# GPIO.net
KiCad netlist of a schematic drawn in Altium Designer
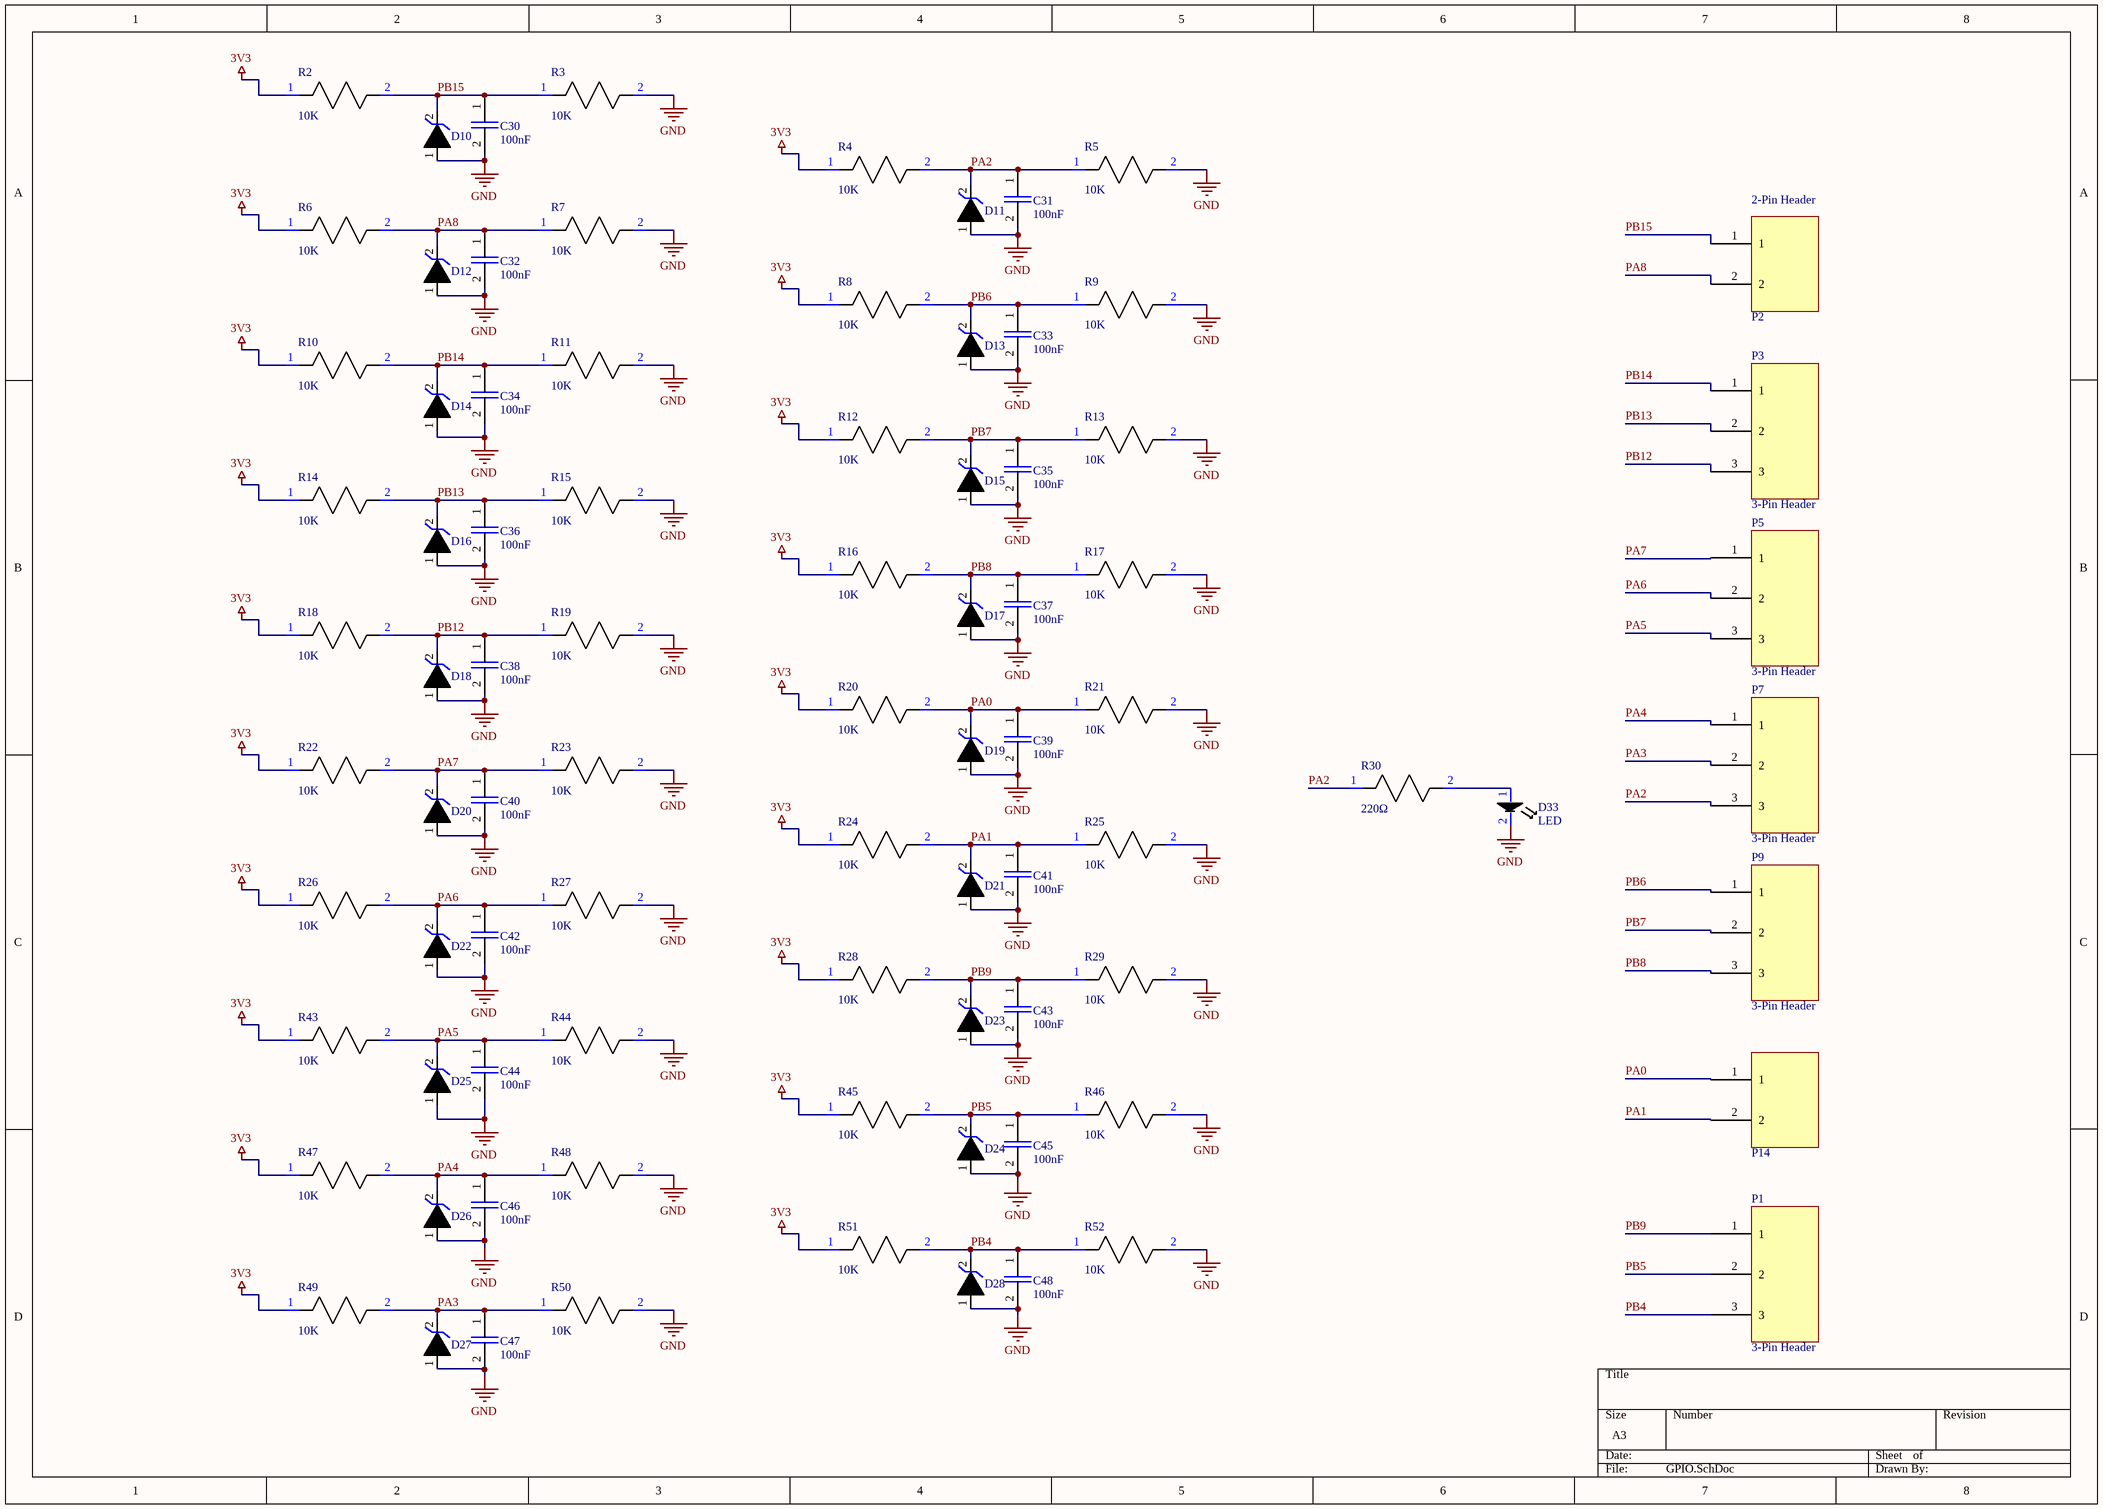
[diagram p0: GPIO.SchDoc]

(export (version "E")
  (design (tool "Eeschema 10.0.6"))
  (components
    (comp (ref "C30")
      (value "100nF")
      (footprint "0603 Cap")
      (description "SMD 0603 (ceramic) capacitor")
      (fields
        (field (name "MANUFACTURER") "Murata")
        (field (name "MANUFACTURER PART NUMBER") "GRM21BR71C225KA12L")
      )
      (libsource (lib "Lib") (part "0603 Cap"))
    )
    (comp (ref "C31")
      (value "100nF")
      (footprint "0603 Cap")
      (description "SMD 0603 (ceramic) capacitor")
      (fields
        (field (name "MANUFACTURER") "Murata")
        (field (name "MANUFACTURER PART NUMBER") "GRM21BR71C225KA12L")
      )
      (libsource (lib "Lib") (part "0603 Cap"))
    )
    (comp (ref "C32")
      (value "100nF")
      (footprint "0603 Cap")
      (description "SMD 0603 (ceramic) capacitor")
      (fields
        (field (name "MANUFACTURER") "Murata")
        (field (name "MANUFACTURER PART NUMBER") "GRM21BR71C225KA12L")
      )
      (libsource (lib "Lib") (part "0603 Cap"))
    )
    (comp (ref "C33")
      (value "100nF")
      (footprint "0603 Cap")
      (description "SMD 0603 (ceramic) capacitor")
      (fields
        (field (name "MANUFACTURER") "Murata")
        (field (name "MANUFACTURER PART NUMBER") "GRM21BR71C225KA12L")
      )
      (libsource (lib "Lib") (part "0603 Cap"))
    )
    (comp (ref "C34")
      (value "100nF")
      (footprint "0603 Cap")
      (description "SMD 0603 (ceramic) capacitor")
      (fields
        (field (name "MANUFACTURER") "Murata")
        (field (name "MANUFACTURER PART NUMBER") "GRM21BR71C225KA12L")
      )
      (libsource (lib "Lib") (part "0603 Cap"))
    )
    (comp (ref "C35")
      (value "100nF")
      (footprint "0603 Cap")
      (description "SMD 0603 (ceramic) capacitor")
      (fields
        (field (name "MANUFACTURER") "Murata")
        (field (name "MANUFACTURER PART NUMBER") "GRM21BR71C225KA12L")
      )
      (libsource (lib "Lib") (part "0603 Cap"))
    )
    (comp (ref "C36")
      (value "100nF")
      (footprint "0603 Cap")
      (description "SMD 0603 (ceramic) capacitor")
      (fields
        (field (name "MANUFACTURER") "Murata")
        (field (name "MANUFACTURER PART NUMBER") "GRM21BR71C225KA12L")
      )
      (libsource (lib "Lib") (part "0603 Cap"))
    )
    (comp (ref "C37")
      (value "100nF")
      (footprint "0603 Cap")
      (description "SMD 0603 (ceramic) capacitor")
      (fields
        (field (name "MANUFACTURER") "Murata")
        (field (name "MANUFACTURER PART NUMBER") "GRM21BR71C225KA12L")
      )
      (libsource (lib "Lib") (part "0603 Cap"))
    )
    (comp (ref "C38")
      (value "100nF")
      (footprint "0603 Cap")
      (description "SMD 0603 (ceramic) capacitor")
      (fields
        (field (name "MANUFACTURER") "Murata")
        (field (name "MANUFACTURER PART NUMBER") "GRM21BR71C225KA12L")
      )
      (libsource (lib "Lib") (part "0603 Cap"))
    )
    (comp (ref "C39")
      (value "100nF")
      (footprint "0603 Cap")
      (description "SMD 0603 (ceramic) capacitor")
      (fields
        (field (name "MANUFACTURER") "Murata")
        (field (name "MANUFACTURER PART NUMBER") "GRM21BR71C225KA12L")
      )
      (libsource (lib "Lib") (part "0603 Cap"))
    )
    (comp (ref "C40")
      (value "100nF")
      (footprint "0603 Cap")
      (description "SMD 0603 (ceramic) capacitor")
      (fields
        (field (name "MANUFACTURER") "Murata")
        (field (name "MANUFACTURER PART NUMBER") "GRM21BR71C225KA12L")
      )
      (libsource (lib "Lib") (part "0603 Cap"))
    )
    (comp (ref "C41")
      (value "100nF")
      (footprint "0603 Cap")
      (description "SMD 0603 (ceramic) capacitor")
      (fields
        (field (name "MANUFACTURER") "Murata")
        (field (name "MANUFACTURER PART NUMBER") "GRM21BR71C225KA12L")
      )
      (libsource (lib "Lib") (part "0603 Cap"))
    )
    (comp (ref "C42")
      (value "100nF")
      (footprint "0603 Cap")
      (description "SMD 0603 (ceramic) capacitor")
      (fields
        (field (name "MANUFACTURER") "Murata")
        (field (name "MANUFACTURER PART NUMBER") "GRM21BR71C225KA12L")
      )
      (libsource (lib "Lib") (part "0603 Cap"))
    )
    (comp (ref "C43")
      (value "100nF")
      (footprint "0603 Cap")
      (description "SMD 0603 (ceramic) capacitor")
      (fields
        (field (name "MANUFACTURER") "Murata")
        (field (name "MANUFACTURER PART NUMBER") "GRM21BR71C225KA12L")
      )
      (libsource (lib "Lib") (part "0603 Cap"))
    )
    (comp (ref "C44")
      (value "100nF")
      (footprint "0603 Cap")
      (description "SMD 0603 (ceramic) capacitor")
      (fields
        (field (name "MANUFACTURER") "Murata")
        (field (name "MANUFACTURER PART NUMBER") "GRM21BR71C225KA12L")
      )
      (libsource (lib "Lib") (part "0603 Cap"))
    )
    (comp (ref "C45")
      (value "100nF")
      (footprint "0603 Cap")
      (description "SMD 0603 (ceramic) capacitor")
      (fields
        (field (name "MANUFACTURER") "Murata")
        (field (name "MANUFACTURER PART NUMBER") "GRM21BR71C225KA12L")
      )
      (libsource (lib "Lib") (part "0603 Cap"))
    )
    (comp (ref "C46")
      (value "100nF")
      (footprint "0603 Cap")
      (description "SMD 0603 (ceramic) capacitor")
      (fields
        (field (name "MANUFACTURER") "Murata")
        (field (name "MANUFACTURER PART NUMBER") "GRM21BR71C225KA12L")
      )
      (libsource (lib "Lib") (part "0603 Cap"))
    )
    (comp (ref "C47")
      (value "100nF")
      (footprint "0603 Cap")
      (description "SMD 0603 (ceramic) capacitor")
      (fields
        (field (name "MANUFACTURER") "Murata")
        (field (name "MANUFACTURER PART NUMBER") "GRM21BR71C225KA12L")
      )
      (libsource (lib "Lib") (part "0603 Cap"))
    )
    (comp (ref "C48")
      (value "100nF")
      (footprint "0603 Cap")
      (description "SMD 0603 (ceramic) capacitor")
      (fields
        (field (name "MANUFACTURER") "Murata")
        (field (name "MANUFACTURER PART NUMBER") "GRM21BR71C225KA12L")
      )
      (libsource (lib "Lib") (part "0603 Cap"))
    )
    (comp (ref "D10")
      (value "TVS")
      (footprint "0805 TVS DIODE")
      (description "Schematic for TVS diode")
      (libsource (lib "Lib") (part "TVS Diode"))
    )
    (comp (ref "D11")
      (value "TVS")
      (footprint "0805 TVS DIODE")
      (description "Schematic for TVS diode")
      (libsource (lib "Lib") (part "TVS Diode"))
    )
    (comp (ref "D12")
      (value "TVS")
      (footprint "0805 TVS DIODE")
      (description "Schematic for TVS diode")
      (libsource (lib "Lib") (part "TVS Diode"))
    )
    (comp (ref "D13")
      (value "TVS")
      (footprint "0805 TVS DIODE")
      (description "Schematic for TVS diode")
      (libsource (lib "Lib") (part "TVS Diode"))
    )
    (comp (ref "D14")
      (value "TVS")
      (footprint "0805 TVS DIODE")
      (description "Schematic for TVS diode")
      (libsource (lib "Lib") (part "TVS Diode"))
    )
    (comp (ref "D15")
      (value "TVS")
      (footprint "0805 TVS DIODE")
      (description "Schematic for TVS diode")
      (libsource (lib "Lib") (part "TVS Diode"))
    )
    (comp (ref "D16")
      (value "TVS")
      (footprint "0805 TVS DIODE")
      (description "Schematic for TVS diode")
      (libsource (lib "Lib") (part "TVS Diode"))
    )
    (comp (ref "D17")
      (value "TVS")
      (footprint "0805 TVS DIODE")
      (description "Schematic for TVS diode")
      (libsource (lib "Lib") (part "TVS Diode"))
    )
    (comp (ref "D18")
      (value "TVS")
      (footprint "0805 TVS DIODE")
      (description "Schematic for TVS diode")
      (libsource (lib "Lib") (part "TVS Diode"))
    )
    (comp (ref "D19")
      (value "TVS")
      (footprint "0805 TVS DIODE")
      (description "Schematic for TVS diode")
      (libsource (lib "Lib") (part "TVS Diode"))
    )
    (comp (ref "D20")
      (value "TVS")
      (footprint "0805 TVS DIODE")
      (description "Schematic for TVS diode")
      (libsource (lib "Lib") (part "TVS Diode"))
    )
    (comp (ref "D21")
      (value "TVS")
      (footprint "0805 TVS DIODE")
      (description "Schematic for TVS diode")
      (libsource (lib "Lib") (part "TVS Diode"))
    )
    (comp (ref "D22")
      (value "TVS")
      (footprint "0805 TVS DIODE")
      (description "Schematic for TVS diode")
      (libsource (lib "Lib") (part "TVS Diode"))
    )
    (comp (ref "D23")
      (value "TVS")
      (footprint "0805 TVS DIODE")
      (description "Schematic for TVS diode")
      (libsource (lib "Lib") (part "TVS Diode"))
    )
    (comp (ref "D24")
      (value "TVS")
      (footprint "0805 TVS DIODE")
      (description "Schematic for TVS diode")
      (libsource (lib "Lib") (part "TVS Diode"))
    )
    (comp (ref "D25")
      (value "TVS")
      (footprint "0805 TVS DIODE")
      (description "Schematic for TVS diode")
      (libsource (lib "Lib") (part "TVS Diode"))
    )
    (comp (ref "D26")
      (value "TVS")
      (footprint "0805 TVS DIODE")
      (description "Schematic for TVS diode")
      (libsource (lib "Lib") (part "TVS Diode"))
    )
    (comp (ref "D27")
      (value "TVS")
      (footprint "0805 TVS DIODE")
      (description "Schematic for TVS diode")
      (libsource (lib "Lib") (part "TVS Diode"))
    )
    (comp (ref "D28")
      (value "TVS")
      (footprint "0805 TVS DIODE")
      (description "Schematic for TVS diode")
      (libsource (lib "Lib") (part "TVS Diode"))
    )
    (comp (ref "D33") (value "LED") (footprint "0805 LED") (libsource (lib "Lib") (part "LED")))
    (comp (ref "P1")
      (value "3-Pin Header")
      (footprint "WR-TBL 322 3H")
      (description "322 Series 3 pin header")
      (libsource (lib "Lib") (part "322-3H"))
    )
    (comp (ref "P2")
      (value "2-Pin Header")
      (footprint "WR-TBL 322 2H")
      (description "322 series 2 pin header")
      (libsource (lib "Lib") (part "322-2H"))
    )
    (comp (ref "P3")
      (value "3-Pin Header")
      (footprint "WR-TBL 322 3H")
      (description "322 Series 3 pin header")
      (libsource (lib "Lib") (part "322-3H"))
    )
    (comp (ref "P5")
      (value "3-Pin Header")
      (footprint "WR-TBL 322 3H")
      (description "322 Series 3 pin header")
      (libsource (lib "Lib") (part "322-3H"))
    )
    (comp (ref "P7")
      (value "3-Pin Header")
      (footprint "WR-TBL 322 3H")
      (description "322 Series 3 pin header")
      (libsource (lib "Lib") (part "322-3H"))
    )
    (comp (ref "P9")
      (value "3-Pin Header")
      (footprint "WR-TBL 322 3H")
      (description "322 Series 3 pin header")
      (libsource (lib "Lib") (part "322-3H"))
    )
    (comp (ref "P14")
      (value "2-Pin Header")
      (footprint "WR-TBL 322 2H")
      (description "322 series 2 pin header")
      (libsource (lib "Lib") (part "322-2H"))
    )
    (comp (ref "R2")
      (value "10K")
      (footprint "0603 RES")
      (description "Can be used for SMD resistors")
      (fields (field (name "Comment") "Resistor"))
      (libsource (lib "Lib") (part "0603 Res"))
    )
    (comp (ref "R3")
      (value "10K")
      (footprint "0603 RES")
      (description "Can be used for SMD resistors")
      (fields (field (name "Comment") "Resistor"))
      (libsource (lib "Lib") (part "0603 Res"))
    )
    (comp (ref "R4")
      (value "10K")
      (footprint "0603 RES")
      (description "Can be used for SMD resistors")
      (fields (field (name "Comment") "Resistor"))
      (libsource (lib "Lib") (part "0603 Res"))
    )
    (comp (ref "R5")
      (value "10K")
      (footprint "0603 RES")
      (description "Can be used for SMD resistors")
      (fields (field (name "Comment") "Resistor"))
      (libsource (lib "Lib") (part "0603 Res"))
    )
    (comp (ref "R6")
      (value "10K")
      (footprint "0603 RES")
      (description "Can be used for SMD resistors")
      (fields (field (name "Comment") "Resistor"))
      (libsource (lib "Lib") (part "0603 Res"))
    )
    (comp (ref "R7")
      (value "10K")
      (footprint "0603 RES")
      (description "Can be used for SMD resistors")
      (fields (field (name "Comment") "Resistor"))
      (libsource (lib "Lib") (part "0603 Res"))
    )
    (comp (ref "R8")
      (value "10K")
      (footprint "0603 RES")
      (description "Can be used for SMD resistors")
      (fields (field (name "Comment") "Resistor"))
      (libsource (lib "Lib") (part "0603 Res"))
    )
    (comp (ref "R9")
      (value "10K")
      (footprint "0603 RES")
      (description "Can be used for SMD resistors")
      (fields (field (name "Comment") "Resistor"))
      (libsource (lib "Lib") (part "0603 Res"))
    )
    (comp (ref "R10")
      (value "10K")
      (footprint "0603 RES")
      (description "Can be used for SMD resistors")
      (fields (field (name "Comment") "Resistor"))
      (libsource (lib "Lib") (part "0603 Res"))
    )
    (comp (ref "R11")
      (value "10K")
      (footprint "0603 RES")
      (description "Can be used for SMD resistors")
      (fields (field (name "Comment") "Resistor"))
      (libsource (lib "Lib") (part "0603 Res"))
    )
    (comp (ref "R12")
      (value "10K")
      (footprint "0603 RES")
      (description "Can be used for SMD resistors")
      (fields (field (name "Comment") "Resistor"))
      (libsource (lib "Lib") (part "0603 Res"))
    )
    (comp (ref "R13")
      (value "10K")
      (footprint "0603 RES")
      (description "Can be used for SMD resistors")
      (fields (field (name "Comment") "Resistor"))
      (libsource (lib "Lib") (part "0603 Res"))
    )
    (comp (ref "R14")
      (value "10K")
      (footprint "0603 RES")
      (description "Can be used for SMD resistors")
      (fields (field (name "Comment") "Resistor"))
      (libsource (lib "Lib") (part "0603 Res"))
    )
    (comp (ref "R15")
      (value "10K")
      (footprint "0603 RES")
      (description "Can be used for SMD resistors")
      (fields (field (name "Comment") "Resistor"))
      (libsource (lib "Lib") (part "0603 Res"))
    )
    (comp (ref "R16")
      (value "10K")
      (footprint "0603 RES")
      (description "Can be used for SMD resistors")
      (fields (field (name "Comment") "Resistor"))
      (libsource (lib "Lib") (part "0603 Res"))
    )
    (comp (ref "R17")
      (value "10K")
      (footprint "0603 RES")
      (description "Can be used for SMD resistors")
      (fields (field (name "Comment") "Resistor"))
      (libsource (lib "Lib") (part "0603 Res"))
    )
    (comp (ref "R18")
      (value "10K")
      (footprint "0603 RES")
      (description "Can be used for SMD resistors")
      (fields (field (name "Comment") "Resistor"))
      (libsource (lib "Lib") (part "0603 Res"))
    )
    (comp (ref "R19")
      (value "10K")
      (footprint "0603 RES")
      (description "Can be used for SMD resistors")
      (fields (field (name "Comment") "Resistor"))
      (libsource (lib "Lib") (part "0603 Res"))
    )
    (comp (ref "R20")
      (value "10K")
      (footprint "0603 RES")
      (description "Can be used for SMD resistors")
      (fields (field (name "Comment") "Resistor"))
      (libsource (lib "Lib") (part "0603 Res"))
    )
    (comp (ref "R21")
      (value "10K")
      (footprint "0603 RES")
      (description "Can be used for SMD resistors")
      (fields (field (name "Comment") "Resistor"))
      (libsource (lib "Lib") (part "0603 Res"))
    )
    (comp (ref "R22")
      (value "10K")
      (footprint "0603 RES")
      (description "Can be used for SMD resistors")
      (fields (field (name "Comment") "Resistor"))
      (libsource (lib "Lib") (part "0603 Res"))
    )
    (comp (ref "R23")
      (value "10K")
      (footprint "0603 RES")
      (description "Can be used for SMD resistors")
      (fields (field (name "Comment") "Resistor"))
      (libsource (lib "Lib") (part "0603 Res"))
    )
    (comp (ref "R24")
      (value "10K")
      (footprint "0603 RES")
      (description "Can be used for SMD resistors")
      (fields (field (name "Comment") "Resistor"))
      (libsource (lib "Lib") (part "0603 Res"))
    )
    (comp (ref "R25")
      (value "10K")
      (footprint "0603 RES")
      (description "Can be used for SMD resistors")
      (fields (field (name "Comment") "Resistor"))
      (libsource (lib "Lib") (part "0603 Res"))
    )
    (comp (ref "R26")
      (value "10K")
      (footprint "0603 RES")
      (description "Can be used for SMD resistors")
      (fields (field (name "Comment") "Resistor"))
      (libsource (lib "Lib") (part "0603 Res"))
    )
    (comp (ref "R27")
      (value "10K")
      (footprint "0603 RES")
      (description "Can be used for SMD resistors")
      (fields (field (name "Comment") "Resistor"))
      (libsource (lib "Lib") (part "0603 Res"))
    )
    (comp (ref "R28")
      (value "10K")
      (footprint "0603 RES")
      (description "Can be used for SMD resistors")
      (fields (field (name "Comment") "Resistor"))
      (libsource (lib "Lib") (part "0603 Res"))
    )
    (comp (ref "R29")
      (value "10K")
      (footprint "0603 RES")
      (description "Can be used for SMD resistors")
      (fields (field (name "Comment") "Resistor"))
      (libsource (lib "Lib") (part "0603 Res"))
    )
    (comp (ref "R30")
      (value "220Ω")
      (footprint "0603 RES")
      (description "Can be used for SMD resistors")
      (fields (field (name "Comment") "Resistor"))
      (libsource (lib "Lib") (part "0603 Res"))
    )
    (comp (ref "R43")
      (value "10K")
      (footprint "0603 RES")
      (description "Can be used for SMD resistors")
      (fields (field (name "Comment") "Resistor"))
      (libsource (lib "Lib") (part "0603 Res"))
    )
    (comp (ref "R44")
      (value "10K")
      (footprint "0603 RES")
      (description "Can be used for SMD resistors")
      (fields (field (name "Comment") "Resistor"))
      (libsource (lib "Lib") (part "0603 Res"))
    )
    (comp (ref "R45")
      (value "10K")
      (footprint "0603 RES")
      (description "Can be used for SMD resistors")
      (fields (field (name "Comment") "Resistor"))
      (libsource (lib "Lib") (part "0603 Res"))
    )
    (comp (ref "R46")
      (value "10K")
      (footprint "0603 RES")
      (description "Can be used for SMD resistors")
      (fields (field (name "Comment") "Resistor"))
      (libsource (lib "Lib") (part "0603 Res"))
    )
    (comp (ref "R47")
      (value "10K")
      (footprint "0603 RES")
      (description "Can be used for SMD resistors")
      (fields (field (name "Comment") "Resistor"))
      (libsource (lib "Lib") (part "0603 Res"))
    )
    (comp (ref "R48")
      (value "10K")
      (footprint "0603 RES")
      (description "Can be used for SMD resistors")
      (fields (field (name "Comment") "Resistor"))
      (libsource (lib "Lib") (part "0603 Res"))
    )
    (comp (ref "R49")
      (value "10K")
      (footprint "0603 RES")
      (description "Can be used for SMD resistors")
      (fields (field (name "Comment") "Resistor"))
      (libsource (lib "Lib") (part "0603 Res"))
    )
    (comp (ref "R50")
      (value "10K")
      (footprint "0603 RES")
      (description "Can be used for SMD resistors")
      (fields (field (name "Comment") "Resistor"))
      (libsource (lib "Lib") (part "0603 Res"))
    )
    (comp (ref "R51")
      (value "10K")
      (footprint "0603 RES")
      (description "Can be used for SMD resistors")
      (fields (field (name "Comment") "Resistor"))
      (libsource (lib "Lib") (part "0603 Res"))
    )
    (comp (ref "R52")
      (value "10K")
      (footprint "0603 RES")
      (description "Can be used for SMD resistors")
      (fields (field (name "Comment") "Resistor"))
      (libsource (lib "Lib") (part "0603 Res"))
    )
  )
  (nets
    (net (code "1") (name "/PA0") (class "Default")
      (node (ref "C39") (pin "1") (pinfunction "11_1") (pintype "passive"))
      (node (ref "D19") (pin "2") (pinfunction "2_2") (pintype "passive"))
      (node (ref "P14") (pin "1") (pinfunction "1_1") (pintype "passive"))
      (node (ref "R20") (pin "2") (pinfunction "21_2") (pintype "passive"))
      (node (ref "R21") (pin "1") (pinfunction "22_1") (pintype "passive"))
    )
    (net (code "2") (name "/PA1") (class "Default")
      (node (ref "C41") (pin "1") (pinfunction "11_1") (pintype "passive"))
      (node (ref "D21") (pin "2") (pinfunction "2_2") (pintype "passive"))
      (node (ref "P14") (pin "2") (pinfunction "2_2") (pintype "passive"))
      (node (ref "R24") (pin "2") (pinfunction "21_2") (pintype "passive"))
      (node (ref "R25") (pin "1") (pinfunction "22_1") (pintype "passive"))
    )
    (net (code "3") (name "/PA2") (class "Default")
      (node (ref "C31") (pin "1") (pinfunction "11_1") (pintype "passive"))
      (node (ref "D11") (pin "2") (pinfunction "2_2") (pintype "passive"))
      (node (ref "P7") (pin "3") (pinfunction "3_3") (pintype "passive"))
      (node (ref "R30") (pin "1") (pinfunction "22_1") (pintype "passive"))
      (node (ref "R4") (pin "2") (pinfunction "21_2") (pintype "passive"))
      (node (ref "R5") (pin "1") (pinfunction "22_1") (pintype "passive"))
    )
    (net (code "4") (name "/PA3") (class "Default")
      (node (ref "C47") (pin "1") (pinfunction "11_1") (pintype "passive"))
      (node (ref "D27") (pin "2") (pinfunction "2_2") (pintype "passive"))
      (node (ref "P7") (pin "2") (pinfunction "2_2") (pintype "passive"))
      (node (ref "R49") (pin "2") (pinfunction "21_2") (pintype "passive"))
      (node (ref "R50") (pin "1") (pinfunction "22_1") (pintype "passive"))
    )
    (net (code "5") (name "/PA4") (class "Default")
      (node (ref "C46") (pin "1") (pinfunction "11_1") (pintype "passive"))
      (node (ref "D26") (pin "2") (pinfunction "2_2") (pintype "passive"))
      (node (ref "P7") (pin "1") (pinfunction "1_1") (pintype "passive"))
      (node (ref "R47") (pin "2") (pinfunction "21_2") (pintype "passive"))
      (node (ref "R48") (pin "1") (pinfunction "22_1") (pintype "passive"))
    )
    (net (code "6") (name "/PA5") (class "Default")
      (node (ref "C44") (pin "1") (pinfunction "11_1") (pintype "passive"))
      (node (ref "D25") (pin "2") (pinfunction "2_2") (pintype "passive"))
      (node (ref "P5") (pin "3") (pinfunction "3_3") (pintype "passive"))
      (node (ref "R43") (pin "2") (pinfunction "21_2") (pintype "passive"))
      (node (ref "R44") (pin "1") (pinfunction "22_1") (pintype "passive"))
    )
    (net (code "7") (name "/PA6") (class "Default")
      (node (ref "C42") (pin "1") (pinfunction "11_1") (pintype "passive"))
      (node (ref "D22") (pin "2") (pinfunction "2_2") (pintype "passive"))
      (node (ref "P5") (pin "2") (pinfunction "2_2") (pintype "passive"))
      (node (ref "R26") (pin "2") (pinfunction "21_2") (pintype "passive"))
      (node (ref "R27") (pin "1") (pinfunction "22_1") (pintype "passive"))
    )
    (net (code "8") (name "/PA7") (class "Default")
      (node (ref "C40") (pin "1") (pinfunction "11_1") (pintype "passive"))
      (node (ref "D20") (pin "2") (pinfunction "2_2") (pintype "passive"))
      (node (ref "P5") (pin "1") (pinfunction "1_1") (pintype "passive"))
      (node (ref "R22") (pin "2") (pinfunction "21_2") (pintype "passive"))
      (node (ref "R23") (pin "1") (pinfunction "22_1") (pintype "passive"))
    )
    (net (code "9") (name "/PA8") (class "Default")
      (node (ref "C32") (pin "1") (pinfunction "11_1") (pintype "passive"))
      (node (ref "D12") (pin "2") (pinfunction "2_2") (pintype "passive"))
      (node (ref "P2") (pin "2") (pinfunction "2_2") (pintype "passive"))
      (node (ref "R6") (pin "2") (pinfunction "21_2") (pintype "passive"))
      (node (ref "R7") (pin "1") (pinfunction "22_1") (pintype "passive"))
    )
    (net (code "10") (name "/PB4") (class "Default")
      (node (ref "C48") (pin "1") (pinfunction "11_1") (pintype "passive"))
      (node (ref "D28") (pin "2") (pinfunction "2_2") (pintype "passive"))
      (node (ref "P1") (pin "3") (pinfunction "3_3") (pintype "passive"))
      (node (ref "R51") (pin "2") (pinfunction "21_2") (pintype "passive"))
      (node (ref "R52") (pin "1") (pinfunction "22_1") (pintype "passive"))
    )
    (net (code "11") (name "/PB5") (class "Default")
      (node (ref "C45") (pin "1") (pinfunction "11_1") (pintype "passive"))
      (node (ref "D24") (pin "2") (pinfunction "2_2") (pintype "passive"))
      (node (ref "P1") (pin "2") (pinfunction "2_2") (pintype "passive"))
      (node (ref "R45") (pin "2") (pinfunction "21_2") (pintype "passive"))
      (node (ref "R46") (pin "1") (pinfunction "22_1") (pintype "passive"))
    )
    (net (code "12") (name "/PB6") (class "Default")
      (node (ref "C33") (pin "1") (pinfunction "11_1") (pintype "passive"))
      (node (ref "D13") (pin "2") (pinfunction "2_2") (pintype "passive"))
      (node (ref "P9") (pin "1") (pinfunction "1_1") (pintype "passive"))
      (node (ref "R8") (pin "2") (pinfunction "21_2") (pintype "passive"))
      (node (ref "R9") (pin "1") (pinfunction "22_1") (pintype "passive"))
    )
    (net (code "13") (name "/PB7") (class "Default")
      (node (ref "C35") (pin "1") (pinfunction "11_1") (pintype "passive"))
      (node (ref "D15") (pin "2") (pinfunction "2_2") (pintype "passive"))
      (node (ref "P9") (pin "2") (pinfunction "2_2") (pintype "passive"))
      (node (ref "R12") (pin "2") (pinfunction "21_2") (pintype "passive"))
      (node (ref "R13") (pin "1") (pinfunction "22_1") (pintype "passive"))
    )
    (net (code "14") (name "/PB8") (class "Default")
      (node (ref "C37") (pin "1") (pinfunction "11_1") (pintype "passive"))
      (node (ref "D17") (pin "2") (pinfunction "2_2") (pintype "passive"))
      (node (ref "P9") (pin "3") (pinfunction "3_3") (pintype "passive"))
      (node (ref "R16") (pin "2") (pinfunction "21_2") (pintype "passive"))
      (node (ref "R17") (pin "1") (pinfunction "22_1") (pintype "passive"))
    )
    (net (code "15") (name "/PB9") (class "Default")
      (node (ref "C43") (pin "1") (pinfunction "11_1") (pintype "passive"))
      (node (ref "D23") (pin "2") (pinfunction "2_2") (pintype "passive"))
      (node (ref "P1") (pin "1") (pinfunction "1_1") (pintype "passive"))
      (node (ref "R28") (pin "2") (pinfunction "21_2") (pintype "passive"))
      (node (ref "R29") (pin "1") (pinfunction "22_1") (pintype "passive"))
    )
    (net (code "16") (name "/PB12") (class "Default")
      (node (ref "C38") (pin "1") (pinfunction "11_1") (pintype "passive"))
      (node (ref "D18") (pin "2") (pinfunction "2_2") (pintype "passive"))
      (node (ref "P3") (pin "3") (pinfunction "3_3") (pintype "passive"))
      (node (ref "R18") (pin "2") (pinfunction "21_2") (pintype "passive"))
      (node (ref "R19") (pin "1") (pinfunction "22_1") (pintype "passive"))
    )
    (net (code "17") (name "/PB13") (class "Default")
      (node (ref "C36") (pin "1") (pinfunction "11_1") (pintype "passive"))
      (node (ref "D16") (pin "2") (pinfunction "2_2") (pintype "passive"))
      (node (ref "P3") (pin "2") (pinfunction "2_2") (pintype "passive"))
      (node (ref "R14") (pin "2") (pinfunction "21_2") (pintype "passive"))
      (node (ref "R15") (pin "1") (pinfunction "22_1") (pintype "passive"))
    )
    (net (code "18") (name "/PB14") (class "Default")
      (node (ref "C34") (pin "1") (pinfunction "11_1") (pintype "passive"))
      (node (ref "D14") (pin "2") (pinfunction "2_2") (pintype "passive"))
      (node (ref "P3") (pin "1") (pinfunction "1_1") (pintype "passive"))
      (node (ref "R10") (pin "2") (pinfunction "21_2") (pintype "passive"))
      (node (ref "R11") (pin "1") (pinfunction "22_1") (pintype "passive"))
    )
    (net (code "19") (name "/PB15") (class "Default")
      (node (ref "C30") (pin "1") (pinfunction "11_1") (pintype "passive"))
      (node (ref "D10") (pin "2") (pinfunction "2_2") (pintype "passive"))
      (node (ref "P2") (pin "1") (pinfunction "1_1") (pintype "passive"))
      (node (ref "R2") (pin "2") (pinfunction "21_2") (pintype "passive"))
      (node (ref "R3") (pin "1") (pinfunction "22_1") (pintype "passive"))
    )
    (net (code "20") (name "3V3") (class "Default")
      (node (ref "R10") (pin "1") (pinfunction "22_1") (pintype "passive"))
      (node (ref "R12") (pin "1") (pinfunction "22_1") (pintype "passive"))
      (node (ref "R14") (pin "1") (pinfunction "22_1") (pintype "passive"))
      (node (ref "R16") (pin "1") (pinfunction "22_1") (pintype "passive"))
      (node (ref "R18") (pin "1") (pinfunction "22_1") (pintype "passive"))
      (node (ref "R2") (pin "1") (pinfunction "22_1") (pintype "passive"))
      (node (ref "R20") (pin "1") (pinfunction "22_1") (pintype "passive"))
      (node (ref "R22") (pin "1") (pinfunction "22_1") (pintype "passive"))
      (node (ref "R24") (pin "1") (pinfunction "22_1") (pintype "passive"))
      (node (ref "R26") (pin "1") (pinfunction "22_1") (pintype "passive"))
      (node (ref "R28") (pin "1") (pinfunction "22_1") (pintype "passive"))
      (node (ref "R4") (pin "1") (pinfunction "22_1") (pintype "passive"))
      (node (ref "R43") (pin "1") (pinfunction "22_1") (pintype "passive"))
      (node (ref "R45") (pin "1") (pinfunction "22_1") (pintype "passive"))
      (node (ref "R47") (pin "1") (pinfunction "22_1") (pintype "passive"))
      (node (ref "R49") (pin "1") (pinfunction "22_1") (pintype "passive"))
      (node (ref "R51") (pin "1") (pinfunction "22_1") (pintype "passive"))
      (node (ref "R6") (pin "1") (pinfunction "22_1") (pintype "passive"))
      (node (ref "R8") (pin "1") (pinfunction "22_1") (pintype "passive"))
    )
    (net (code "21") (name "GND") (class "Default")
      (node (ref "C30") (pin "2") (pinfunction "12_2") (pintype "passive"))
      (node (ref "C31") (pin "2") (pinfunction "12_2") (pintype "passive"))
      (node (ref "C32") (pin "2") (pinfunction "12_2") (pintype "passive"))
      (node (ref "C33") (pin "2") (pinfunction "12_2") (pintype "passive"))
      (node (ref "C34") (pin "2") (pinfunction "12_2") (pintype "passive"))
      (node (ref "C35") (pin "2") (pinfunction "12_2") (pintype "passive"))
      (node (ref "C36") (pin "2") (pinfunction "12_2") (pintype "passive"))
      (node (ref "C37") (pin "2") (pinfunction "12_2") (pintype "passive"))
      (node (ref "C38") (pin "2") (pinfunction "12_2") (pintype "passive"))
      (node (ref "C39") (pin "2") (pinfunction "12_2") (pintype "passive"))
      (node (ref "C40") (pin "2") (pinfunction "12_2") (pintype "passive"))
      (node (ref "C41") (pin "2") (pinfunction "12_2") (pintype "passive"))
      (node (ref "C42") (pin "2") (pinfunction "12_2") (pintype "passive"))
      (node (ref "C43") (pin "2") (pinfunction "12_2") (pintype "passive"))
      (node (ref "C44") (pin "2") (pinfunction "12_2") (pintype "passive"))
      (node (ref "C45") (pin "2") (pinfunction "12_2") (pintype "passive"))
      (node (ref "C46") (pin "2") (pinfunction "12_2") (pintype "passive"))
      (node (ref "C47") (pin "2") (pinfunction "12_2") (pintype "passive"))
      (node (ref "C48") (pin "2") (pinfunction "12_2") (pintype "passive"))
      (node (ref "D10") (pin "1") (pinfunction "1_1") (pintype "passive"))
      (node (ref "D11") (pin "1") (pinfunction "1_1") (pintype "passive"))
      (node (ref "D12") (pin "1") (pinfunction "1_1") (pintype "passive"))
      (node (ref "D13") (pin "1") (pinfunction "1_1") (pintype "passive"))
      (node (ref "D14") (pin "1") (pinfunction "1_1") (pintype "passive"))
      (node (ref "D15") (pin "1") (pinfunction "1_1") (pintype "passive"))
      (node (ref "D16") (pin "1") (pinfunction "1_1") (pintype "passive"))
      (node (ref "D17") (pin "1") (pinfunction "1_1") (pintype "passive"))
      (node (ref "D18") (pin "1") (pinfunction "1_1") (pintype "passive"))
      (node (ref "D19") (pin "1") (pinfunction "1_1") (pintype "passive"))
      (node (ref "D20") (pin "1") (pinfunction "1_1") (pintype "passive"))
      (node (ref "D21") (pin "1") (pinfunction "1_1") (pintype "passive"))
      (node (ref "D22") (pin "1") (pinfunction "1_1") (pintype "passive"))
      (node (ref "D23") (pin "1") (pinfunction "1_1") (pintype "passive"))
      (node (ref "D24") (pin "1") (pinfunction "1_1") (pintype "passive"))
      (node (ref "D25") (pin "1") (pinfunction "1_1") (pintype "passive"))
      (node (ref "D26") (pin "1") (pinfunction "1_1") (pintype "passive"))
      (node (ref "D27") (pin "1") (pinfunction "1_1") (pintype "passive"))
      (node (ref "D28") (pin "1") (pinfunction "1_1") (pintype "passive"))
      (node (ref "D33") (pin "2") (pinfunction "2_2") (pintype "passive"))
      (node (ref "R11") (pin "2") (pinfunction "21_2") (pintype "passive"))
      (node (ref "R13") (pin "2") (pinfunction "21_2") (pintype "passive"))
      (node (ref "R15") (pin "2") (pinfunction "21_2") (pintype "passive"))
      (node (ref "R17") (pin "2") (pinfunction "21_2") (pintype "passive"))
      (node (ref "R19") (pin "2") (pinfunction "21_2") (pintype "passive"))
      (node (ref "R21") (pin "2") (pinfunction "21_2") (pintype "passive"))
      (node (ref "R23") (pin "2") (pinfunction "21_2") (pintype "passive"))
      (node (ref "R25") (pin "2") (pinfunction "21_2") (pintype "passive"))
      (node (ref "R27") (pin "2") (pinfunction "21_2") (pintype "passive"))
      (node (ref "R29") (pin "2") (pinfunction "21_2") (pintype "passive"))
      (node (ref "R3") (pin "2") (pinfunction "21_2") (pintype "passive"))
      (node (ref "R44") (pin "2") (pinfunction "21_2") (pintype "passive"))
      (node (ref "R46") (pin "2") (pinfunction "21_2") (pintype "passive"))
      (node (ref "R48") (pin "2") (pinfunction "21_2") (pintype "passive"))
      (node (ref "R5") (pin "2") (pinfunction "21_2") (pintype "passive"))
      (node (ref "R50") (pin "2") (pinfunction "21_2") (pintype "passive"))
      (node (ref "R52") (pin "2") (pinfunction "21_2") (pintype "passive"))
      (node (ref "R7") (pin "2") (pinfunction "21_2") (pintype "passive"))
      (node (ref "R9") (pin "2") (pinfunction "21_2") (pintype "passive"))
    )
    (net (code "22") (name "Net-(R30-21)") (class "Default")
      (node (ref "D33") (pin "1") (pinfunction "1_1") (pintype "passive"))
      (node (ref "R30") (pin "2") (pinfunction "21_2") (pintype "passive"))
    )
  )
)
